# CheeseCake-BMI270-RV.net
KiCad netlist of a schematic drawn in EasyEDA Pro
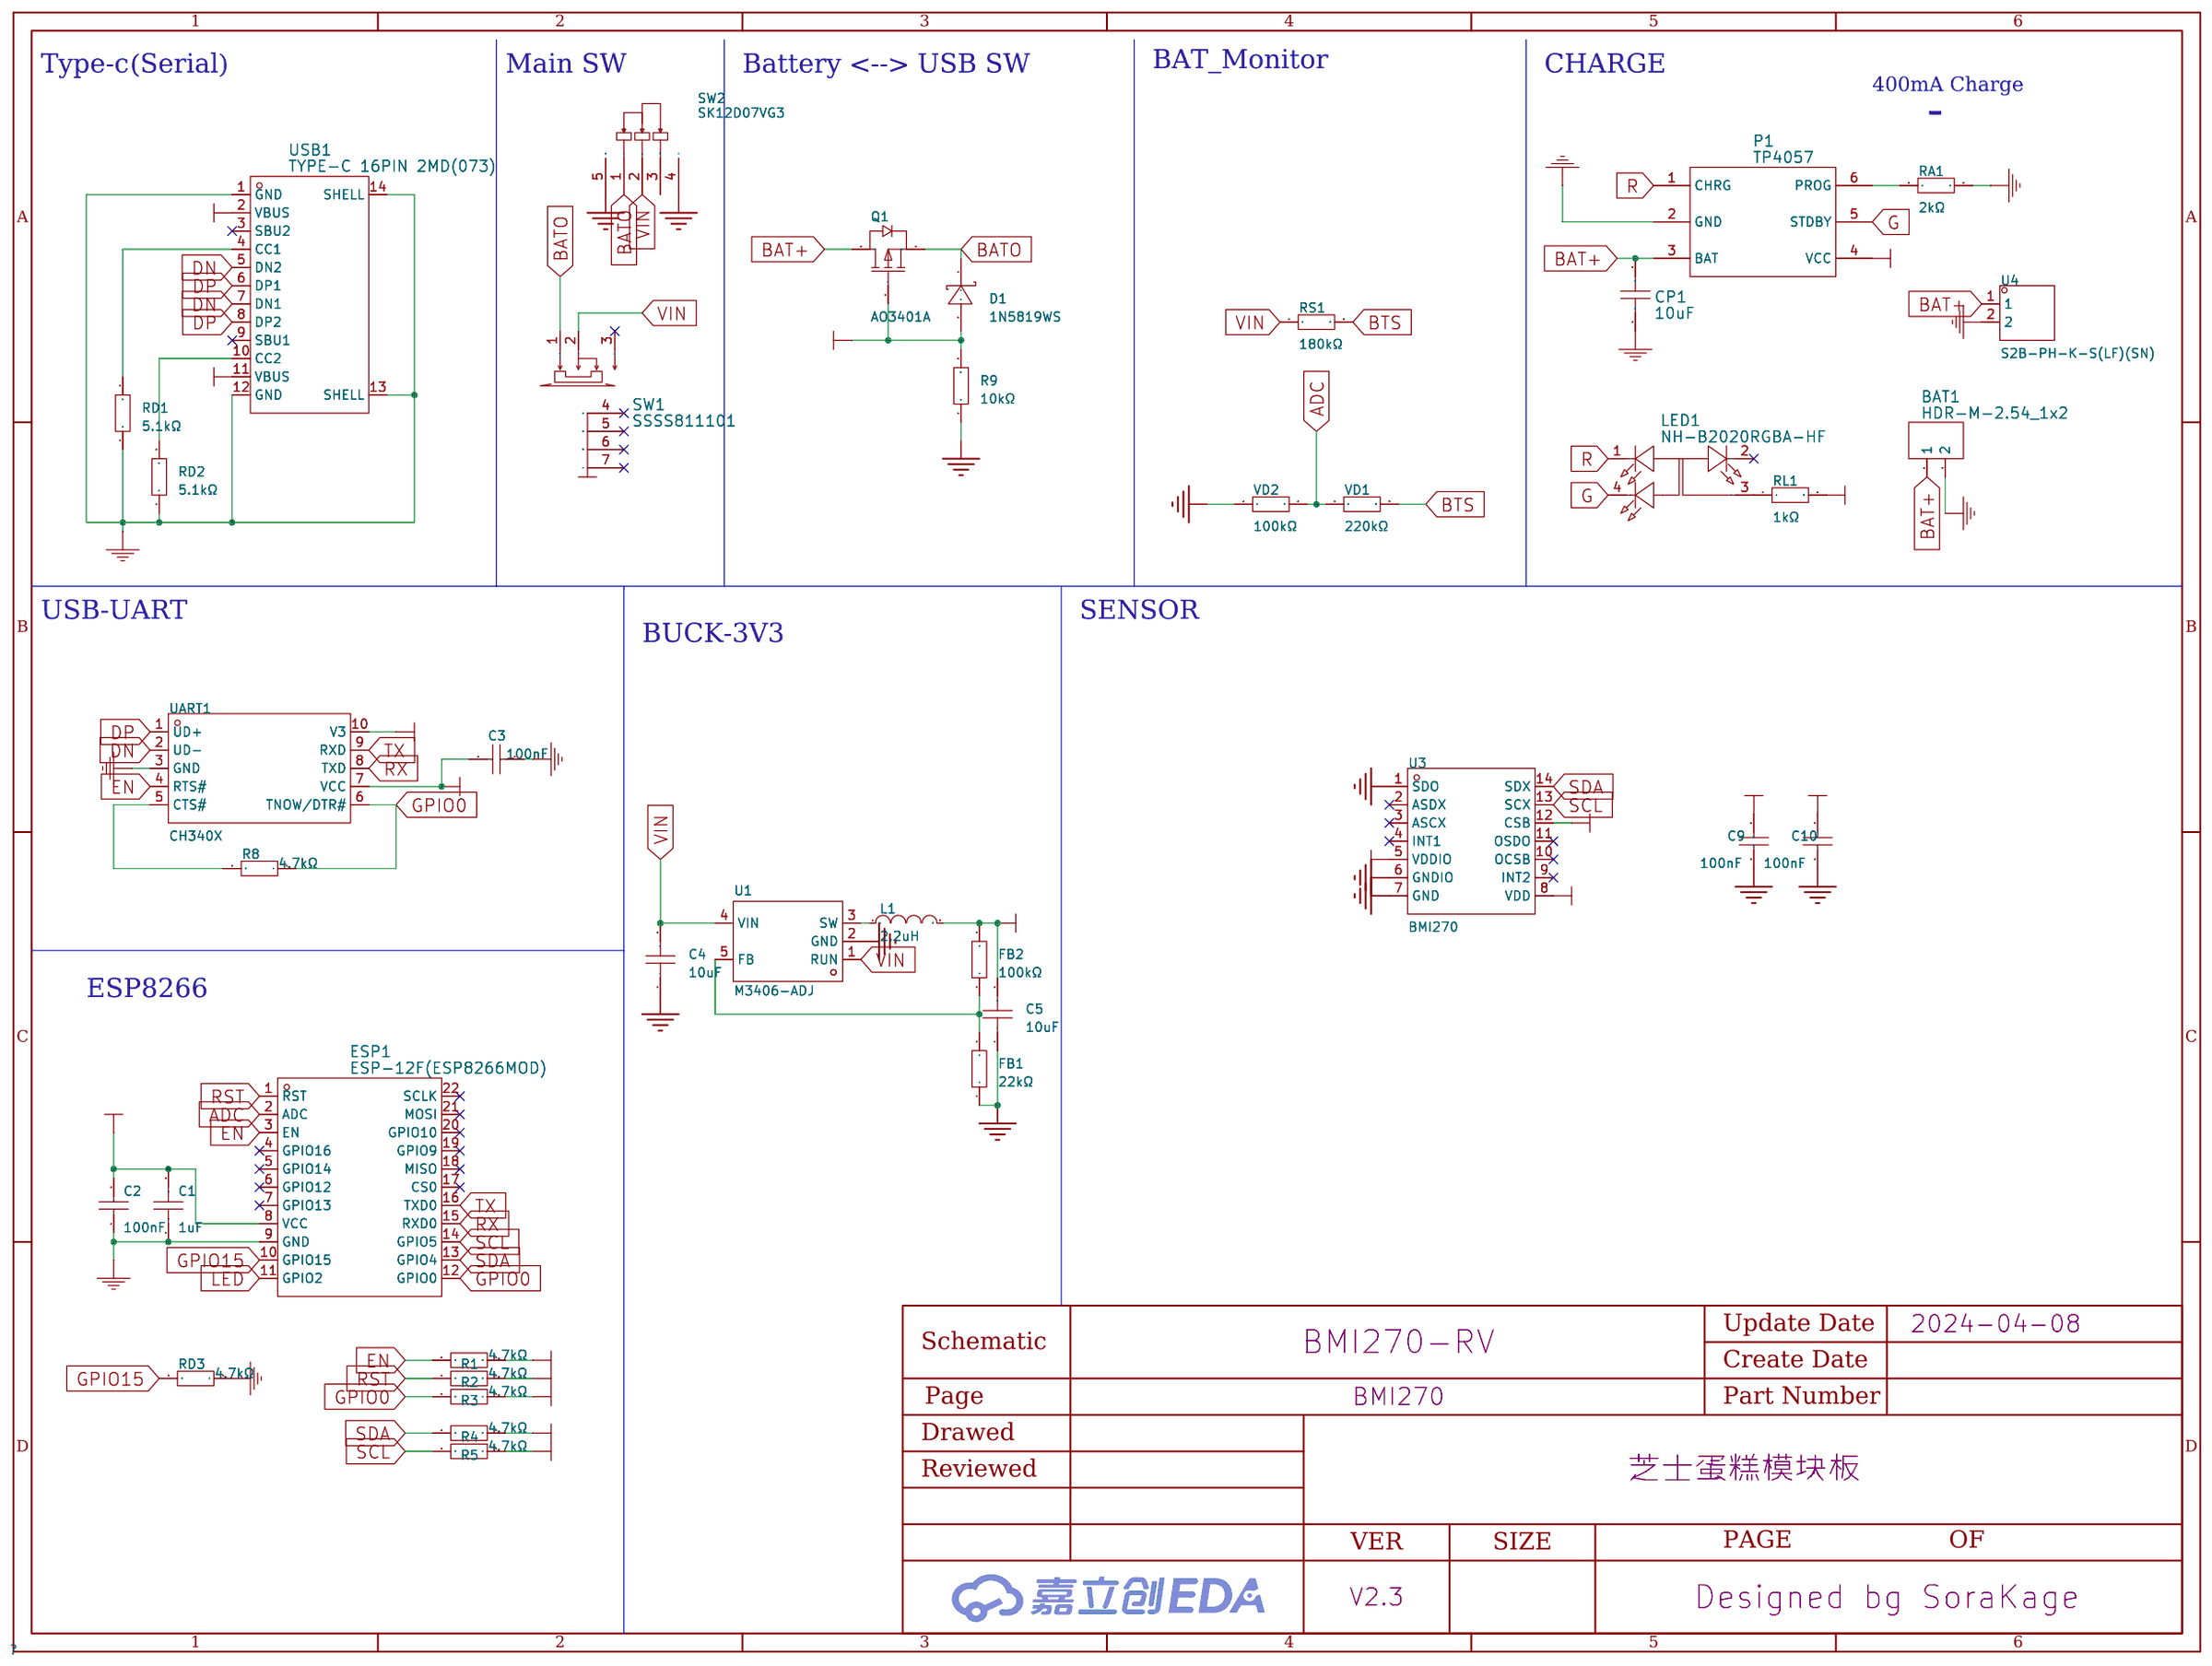
[diagram p0: schematic sheet]

(export (version "E")
  (design (tool "Eeschema 10.0.6"))
  (components
    (comp (ref "BAT1")
      (value "HDR-M-2.54_1x2")
      (footprint "easyedapro:HDR-M-2.54_1X2")
      (libsource (lib "easyedapro") (part "HDR-M-2.54_1x2"))
    )
    (comp (ref "C1")
      (value "1uF")
      (footprint "easyedapro:C0402")
      (description "容值:1uF;精度:±10%;额定电压:25V;材质(温度系数):X5R;")
      (fields
        (field (name "Manufacturer Part") "CL05A105KA5NQNC")
        (field (name "Manufacturer") "SAMSUNG(三星)")
      )
      (libsource (lib "easyedapro") (part "CL05A105KA5NQNC"))
    )
    (comp (ref "C2")
      (value "100nF")
      (footprint "easyedapro:C0402")
      (description "容值:100nF;精度:±10%;额定电压:16V;材质(温度系数):X7R;")
      (fields
        (field (name "Manufacturer Part") "CL05B104KO5NNNC")
        (field (name "Manufacturer") "SAMSUNG(三星)")
      )
      (libsource (lib "easyedapro") (part "CL05B104KO5NNNC"))
    )
    (comp (ref "C3")
      (value "100nF")
      (footprint "easyedapro:C0402")
      (description "容值:100nF;精度:±10%;额定电压:16V;材质(温度系数):X7R;")
      (fields
        (field (name "Manufacturer Part") "CL05B104KO5NNNC")
        (field (name "Manufacturer") "SAMSUNG(三星)")
      )
      (libsource (lib "easyedapro") (part "CL05B104KO5NNNC"))
    )
    (comp (ref "C4")
      (value "10uF")
      (footprint "easyedapro:C0603")
      (description "容值:10uF;精度:±10%;额定电压:10V;材质(温度系数):X5R;")
      (fields
        (field (name "Manufacturer Part") "CL10A106KP8NNNC")
        (field (name "Manufacturer") "SAMSUNG(三星)")
      )
      (libsource (lib "easyedapro") (part "CL10A106KP8NNNC"))
    )
    (comp (ref "C5")
      (value "10uF")
      (footprint "easyedapro:C0603")
      (description "容值:10uF;精度:±10%;额定电压:10V;材质(温度系数):X5R;")
      (fields
        (field (name "Manufacturer Part") "CL10A106KP8NNNC")
        (field (name "Manufacturer") "SAMSUNG(三星)")
      )
      (libsource (lib "easyedapro") (part "CL10A106KP8NNNC"))
    )
    (comp (ref "C9")
      (value "100nF")
      (footprint "easyedapro:C0402")
      (description "容值:100nF;精度:±10%;额定电压:16V;材质(温度系数):X7R;")
      (fields
        (field (name "Manufacturer Part") "CL05B104KO5NNNC")
        (field (name "Manufacturer") "SAMSUNG(三星)")
      )
      (libsource (lib "easyedapro") (part "CL05B104KO5NNNC"))
    )
    (comp (ref "C10")
      (value "100nF")
      (footprint "easyedapro:C0402")
      (description "容值:100nF;精度:±10%;额定电压:16V;材质(温度系数):X7R;")
      (fields
        (field (name "Manufacturer Part") "CL05B104KO5NNNC")
        (field (name "Manufacturer") "SAMSUNG(三星)")
      )
      (libsource (lib "easyedapro") (part "CL05B104KO5NNNC"))
    )
    (comp (ref "CP1")
      (value "10uF")
      (footprint "easyedapro:C0603")
      (fields
        (field (name "Manufacturer Part") "CL10A106KP8NNNC")
        (field (name "Manufacturer") "SAMSUNG(三星)")
      )
      (libsource (lib "easyedapro") (part "10uF"))
    )
    (comp (ref "D1")
      (value "1N5819WS")
      (footprint "easyedapro:SOD-323_L1.8-W1.3-LS2.5-RD")
      (description "直流反向耐压(Vr):40V;平均整流电流(Io):1A;正向压降(Vf):600mV@1A;")
      (fields (field (name "Manufacturer") "Hottech(合科泰)"))
      (libsource (lib "easyedapro") (part "1N5819WS"))
    )
    (comp (ref "ESP1")
      (value "ESP-12F(ESP8266MOD)")
      (fields (field (name "Manufacturer") "Ai-Thinker"))
      (libsource (lib "easyedapro") (part "ESP-12F(ESP8266MOD)"))
    )
    (comp (ref "FB1")
      (value "22kΩ")
      (footprint "easyedapro:R0402")
      (description "电阻类型:厚膜电阻;阻值:22kΩ;精度:±1%;功率:62.5mW;")
      (fields
        (field (name "Manufacturer Part") "0402WGF2202TCE")
        (field (name "Manufacturer") "UNI-ROYAL(厚声)")
      )
      (libsource (lib "easyedapro") (part "0402WGF2202TCE"))
    )
    (comp (ref "FB2")
      (value "100kΩ")
      (footprint "easyedapro:R0402")
      (description "电阻类型:厚膜电阻;阻值:100kΩ;精度:±1%;功率:62.5mW;")
      (fields
        (field (name "Manufacturer Part") "0402WGF1003TCE")
        (field (name "Manufacturer") "UNI-ROYAL(厚声)")
      )
      (libsource (lib "easyedapro") (part "0402WGF1003TCE"))
    )
    (comp (ref "L1")
      (value "2.2uH")
      (footprint "easyedapro:IND-SMD_L2.5-W2.0_YXMBL252010P")
      (description "类型:一体成型电感;电感值:2.2uH;精度:±20%;额定电流:2.1A;饱和电流(Isat):3A;")
      (fields (field (name "Manufacturer Part") "APH252010T2R2M") (field (name "Manufacturer") "APV(爱普微)"))
      (libsource (lib "easyedapro") (part "APH252010T2R2M"))
    )
    (comp (ref "LED1")
      (value "NH-B2020RGBA-HF")
      (footprint "easyedapro:LED-ARRAY-SMD_4P-L2.1-W2.1-TL_NH-B2020RGBA")
      (fields (field (name "Manufacturer") "国星光电"))
      (libsource (lib "easyedapro") (part "NH-B2020RGBA-HF"))
    )
    (comp (ref "P1")
      (value "TP4057")
      (fields
        (field (name "Manufacturer Part") "TP4057-42-SOT26-R")
        (field (name "Manufacturer") "TOPPOWER(南京拓微)")
      )
      (libsource (lib "easyedapro") (part "TP4057"))
    )
    (comp (ref "Q1")
      (value "AO3401A")
      (footprint "easyedapro:SOT-23_L2.9-W1.3-P1.90-LS2.4-BR")
      (description "类型:P沟道;漏源电压(Vdss):30V;连续漏极电流(Id):4A;功率(Pd):1.4W;导通电阻(RDS(on)@Vgs,Id):44mΩ@10V,4.3A;")
      (fields (field (name "Manufacturer") "AOS"))
      (libsource (lib "easyedapro") (part "AO3401A"))
    )
    (comp (ref "R1")
      (value "4.7kΩ")
      (footprint "easyedapro:R0402")
      (description "电阻类型:厚膜电阻;阻值:4.7kΩ;精度:±1%;功率:62.5mW;")
      (fields
        (field (name "Manufacturer Part") "0402WGF4701TCE")
        (field (name "Manufacturer") "UNI-ROYAL(厚声)")
      )
      (libsource (lib "easyedapro") (part "0402WGF4701TCE"))
    )
    (comp (ref "R2")
      (value "4.7kΩ")
      (footprint "easyedapro:R0402")
      (description "电阻类型:厚膜电阻;阻值:4.7kΩ;精度:±1%;功率:62.5mW;")
      (fields
        (field (name "Manufacturer Part") "0402WGF4701TCE")
        (field (name "Manufacturer") "UNI-ROYAL(厚声)")
      )
      (libsource (lib "easyedapro") (part "0402WGF4701TCE"))
    )
    (comp (ref "R3")
      (value "4.7kΩ")
      (footprint "easyedapro:R0402")
      (description "电阻类型:厚膜电阻;阻值:4.7kΩ;精度:±1%;功率:62.5mW;")
      (fields
        (field (name "Manufacturer Part") "0402WGF4701TCE")
        (field (name "Manufacturer") "UNI-ROYAL(厚声)")
      )
      (libsource (lib "easyedapro") (part "0402WGF4701TCE"))
    )
    (comp (ref "R4")
      (value "4.7kΩ")
      (footprint "easyedapro:R0402")
      (description "电阻类型:厚膜电阻;阻值:4.7kΩ;精度:±1%;功率:62.5mW;")
      (fields
        (field (name "Manufacturer Part") "0402WGF4701TCE")
        (field (name "Manufacturer") "UNI-ROYAL(厚声)")
      )
      (libsource (lib "easyedapro") (part "0402WGF4701TCE"))
    )
    (comp (ref "R5")
      (value "4.7kΩ")
      (footprint "easyedapro:R0402")
      (description "电阻类型:厚膜电阻;阻值:4.7kΩ;精度:±1%;功率:62.5mW;")
      (fields
        (field (name "Manufacturer Part") "0402WGF4701TCE")
        (field (name "Manufacturer") "UNI-ROYAL(厚声)")
      )
      (libsource (lib "easyedapro") (part "0402WGF4701TCE"))
    )
    (comp (ref "R8")
      (value "4.7kΩ")
      (footprint "easyedapro:R0402")
      (description "电阻类型:厚膜电阻;阻值:4.7kΩ;精度:±1%;功率:62.5mW;")
      (fields
        (field (name "Manufacturer Part") "0402WGF4701TCE")
        (field (name "Manufacturer") "UNI-ROYAL(厚声)")
      )
      (libsource (lib "easyedapro") (part "0402WGF4701TCE"))
    )
    (comp (ref "R9")
      (value "10kΩ")
      (footprint "easyedapro:R0402")
      (description "电阻类型:厚膜电阻;阻值:10kΩ;精度:±1%;功率:62.5mW;")
      (fields
        (field (name "Manufacturer Part") "0402WGF1002TCE")
        (field (name "Manufacturer") "UNI-ROYAL(厚声)")
      )
      (libsource (lib "easyedapro") (part "0402WGF1002TCE"))
    )
    (comp (ref "RA1")
      (value "2kΩ")
      (footprint "easyedapro:R0402")
      (description "电阻类型:厚膜电阻;阻值:2kΩ;精度:±1%;功率:62.5mW;")
      (fields
        (field (name "Manufacturer Part") "0402WGF2001TCE")
        (field (name "Manufacturer") "UNI-ROYAL(厚声)")
      )
      (libsource (lib "easyedapro") (part "0402WGF2001TCE"))
    )
    (comp (ref "RD1")
      (value "5.1kΩ")
      (footprint "easyedapro:R0402")
      (description "电阻类型:厚膜电阻;阻值:5.1kΩ;精度:±1%;功率:62.5mW;")
      (fields
        (field (name "Manufacturer Part") "0402WGF5101TCE")
        (field (name "Manufacturer") "UNI-ROYAL(厚声)")
      )
      (libsource (lib "easyedapro") (part "0402WGF5101TCE"))
    )
    (comp (ref "RD2")
      (value "5.1kΩ")
      (footprint "easyedapro:R0402")
      (description "电阻类型:厚膜电阻;阻值:5.1kΩ;精度:±1%;功率:62.5mW;")
      (fields
        (field (name "Manufacturer Part") "0402WGF5101TCE")
        (field (name "Manufacturer") "UNI-ROYAL(厚声)")
      )
      (libsource (lib "easyedapro") (part "0402WGF5101TCE"))
    )
    (comp (ref "RD3")
      (value "4.7kΩ")
      (footprint "easyedapro:R0402")
      (description "电阻类型:厚膜电阻;阻值:4.7kΩ;精度:±1%;功率:62.5mW;")
      (fields
        (field (name "Manufacturer Part") "0402WGF4701TCE")
        (field (name "Manufacturer") "UNI-ROYAL(厚声)")
      )
      (libsource (lib "easyedapro") (part "0402WGF4701TCE"))
    )
    (comp (ref "RL1")
      (value "1kΩ")
      (footprint "easyedapro:R0402")
      (description "电阻类型:厚膜电阻;阻值:1kΩ;精度:±1%;功率:62.5mW;")
      (fields
        (field (name "Manufacturer Part") "0402WGF1001TCE")
        (field (name "Manufacturer") "UNI-ROYAL(厚声)")
      )
      (libsource (lib "easyedapro") (part "0402WGF1001TCE"))
    )
    (comp (ref "RS1")
      (value "180kΩ")
      (footprint "easyedapro:R0402")
      (description "阻值:180kΩ;精度:±1%;功率:62.5mW;温度系数:±100ppm/°C;电阻类型:厚膜电阻;")
      (fields
        (field (name "Manufacturer Part") "0402WGF1803TCE")
        (field (name "Manufacturer") "UNI-ROYAL(厚声)")
      )
      (libsource (lib "easyedapro") (part "0402WGF1803TCE"))
    )
    (comp (ref "SW1")
      (value "SSSS811101")
      (footprint "easyedapro:SW-SMD_SSSS811101")
      (fields (field (name "Manufacturer") "ALPSALPINE(阿尔卑斯阿尔派)"))
      (libsource (lib "easyedapro") (part "SSSS811101"))
    )
    (comp (ref "SW2")
      (value "SK12D07VG3")
      (footprint "easyedapro:SW-TH_SK12D07VG3")
      (description "电路结构:单刀双掷;安装方式:侧插;开关颜色:-;额定电流(DC):500mA;额定电压(DC):50V;额定电流(AC):-;额定电压(AC):-;机械寿命:5千次;")
      (fields (field (name "Manufacturer") "SHOU HAN(首韩)"))
      (libsource (lib "easyedapro") (part "SK12D07VG3_C431547"))
    )
    (comp (ref "U1")
      (value "M3406-ADJ")
      (footprint "easyedapro:SOT-23-5_L3.0-W1.7-P0.95-LS2.8-BR")
      (description "功能类型:降压型;同步整流:-;输出通道数:-;拓扑结构:-;输入电压:-;输出电流(最大值):-;开关频率:-;")
      (fields (field (name "Manufacturer") "西安航天民芯"))
      (libsource (lib "easyedapro") (part "M3406"))
    )
    (comp (ref "U3")
      (value "BMI270")
      (footprint "easyedapro:LGA-14_L3.0-W2.5-P0.50-BR")
      (description "IMU-惯性测量单元")
      (fields (field (name "Manufacturer") "Bosch(博世)"))
      (libsource (lib "easyedapro") (part "BMI270"))
    )
    (comp (ref "U4")
      (value "S2B-PH-K-S(LF)(SN)")
      (footprint "easyedapro:CONN-TH_S2B-PH-K-S-LF-SN")
      (description "插针结构:1x2P;间距:2mm;安装方式:弯插;参考系列:PH;总PIN数:2P;排数:1;每排PIN数:2;行距:-;触头材质:黄铜;")
      (fields (field (name "Manufacturer") "JST"))
      (libsource (lib "easyedapro") (part "S2B-PH-K-S(LF)(SN)"))
    )
    (comp (ref "UART1")
      (value "CH340X")
      (footprint "easyedapro:MSOP-10_L3.0-W3.0-P0.50-LS5.0-BL")
      (fields (field (name "Manufacturer") "WCH(南京沁恒)"))
      (libsource (lib "easyedapro") (part "CH340X"))
    )
    (comp (ref "USB1")
      (value "TYPE-C 16PIN 2MD(073)")
      (footprint "easyedapro:USB-C-SMD_TYPE-C-6PIN-2MD-073")
      (fields (field (name "Manufacturer") "SHOU HAN(首韩)"))
      (libsource (lib "easyedapro") (part "TYPE-C 16PIN 2MD(073)"))
    )
    (comp (ref "VD1")
      (value "220kΩ")
      (footprint "easyedapro:R0402")
      (description "电阻类型:厚膜电阻;阻值:220kΩ;精度:±1%;功率:62.5mW;")
      (fields
        (field (name "Manufacturer Part") "0402WGF2203TCE")
        (field (name "Manufacturer") "UNI-ROYAL(厚声)")
      )
      (libsource (lib "easyedapro") (part "0402WGF2203TCE"))
    )
    (comp (ref "VD2")
      (value "100kΩ")
      (footprint "easyedapro:R0402")
      (description "电阻类型:厚膜电阻;阻值:100kΩ;精度:±1%;功率:62.5mW;")
      (fields
        (field (name "Manufacturer Part") "0402WGF1003TCE")
        (field (name "Manufacturer") "UNI-ROYAL(厚声)")
      )
      (libsource (lib "easyedapro") (part "0402WGF1003TCE"))
    )
  )
  (nets
    (net (code "1") (name "+5V") (class "Default")
      (node (ref "D1") (pin "2") (pinfunction "A_2") (pintype "unspecified"))
      (node (ref "P1") (pin "4") (pinfunction "VCC_4") (pintype "input"))
      (node (ref "Q1") (pin "1") (pinfunction "G_1") (pintype "input"))
      (node (ref "R9") (pin "2") (pinfunction "2_2") (pintype "input"))
      (node (ref "RL1") (pin "2") (pinfunction "2_2") (pintype "input"))
      (node (ref "USB1") (pin "11") (pinfunction "VBUS_11") (pintype "input"))
      (node (ref "USB1") (pin "2") (pinfunction "VBUS_2") (pintype "input"))
    )
    (net (code "2") (name "3V3") (class "Default")
      (node (ref "C1") (pin "2") (pinfunction "2_2") (pintype "unspecified"))
      (node (ref "C10") (pin "1") (pinfunction "1_1") (pintype "input"))
      (node (ref "C2") (pin "2") (pinfunction "2_2") (pintype "input"))
      (node (ref "C3") (pin "2") (pinfunction "2_2") (pintype "input"))
      (node (ref "C5") (pin "2") (pinfunction "2_2") (pintype "unspecified"))
      (node (ref "C9") (pin "1") (pinfunction "1_1") (pintype "input"))
      (node (ref "ESP1") (pin "8") (pinfunction "VCC_8") (pintype "input"))
      (node (ref "FB2") (pin "2") (pinfunction "2_2") (pintype "input"))
      (node (ref "L1") (pin "2") (pinfunction "2_2") (pintype "unspecified"))
      (node (ref "R1") (pin "1") (pinfunction "1_1") (pintype "input"))
      (node (ref "R2") (pin "1") (pinfunction "1_1") (pintype "input"))
      (node (ref "R3") (pin "1") (pinfunction "1_1") (pintype "input"))
      (node (ref "R4") (pin "1") (pinfunction "1_1") (pintype "input"))
      (node (ref "R5") (pin "1") (pinfunction "1_1") (pintype "input"))
      (node (ref "U3") (pin "12") (pinfunction "CSB_12") (pintype "input"))
      (node (ref "U3") (pin "5") (pinfunction "VDDIO_5") (pintype "input"))
      (node (ref "U3") (pin "8") (pinfunction "VDD_8") (pintype "input"))
      (node (ref "UART1") (pin "10") (pinfunction "V3_10") (pintype "unspecified"))
      (node (ref "UART1") (pin "7") (pinfunction "VCC_7") (pintype "unspecified"))
    )
    (net (code "3") (name "ADC") (class "Default")
      (node (ref "ESP1") (pin "2") (pinfunction "ADC_2") (pintype "input"))
      (node (ref "VD1") (pin "1") (pinfunction "1_1") (pintype "input"))
      (node (ref "VD2") (pin "2") (pinfunction "2_2") (pintype "input"))
    )
    (net (code "4") (name "BAT+") (class "Default")
      (node (ref "BAT1") (pin "1") (pinfunction "1_1") (pintype "input"))
      (node (ref "CP1") (pin "2") (pinfunction "2_2") (pintype "input"))
      (node (ref "P1") (pin "3") (pinfunction "BAT_3") (pintype "input"))
      (node (ref "Q1") (pin "3") (pinfunction "D_3") (pintype "input"))
      (node (ref "U4") (pin "1") (pinfunction "1_1") (pintype "unspecified"))
    )
    (net (code "5") (name "BATO") (class "Default")
      (node (ref "D1") (pin "1") (pinfunction "K_1") (pintype "unspecified"))
      (node (ref "Q1") (pin "2") (pinfunction "S_2") (pintype "input"))
      (node (ref "SW1") (pin "1") (pinfunction "1_1") (pintype "input"))
      (node (ref "SW2") (pin "1") (pinfunction "1_1") (pintype "unspecified"))
    )
    (net (code "6") (name "BTS") (class "Default")
      (node (ref "RS1") (pin "2") (pinfunction "2_2") (pintype "input"))
      (node (ref "VD1") (pin "2") (pinfunction "2_2") (pintype "input"))
    )
    (net (code "7") (name "DN") (class "Default")
      (node (ref "UART1") (pin "2") (pinfunction "UD-_2") (pintype "unspecified"))
      (node (ref "USB1") (pin "5") (pinfunction "DN2_5") (pintype "input"))
      (node (ref "USB1") (pin "7") (pinfunction "DN1_7") (pintype "input"))
    )
    (net (code "8") (name "DP") (class "Default")
      (node (ref "UART1") (pin "1") (pinfunction "UD+_1") (pintype "unspecified"))
      (node (ref "USB1") (pin "6") (pinfunction "DP1_6") (pintype "input"))
      (node (ref "USB1") (pin "8") (pinfunction "DP2_8") (pintype "input"))
    )
    (net (code "9") (name "EN") (class "Default")
      (node (ref "ESP1") (pin "3") (pinfunction "EN_3") (pintype "input"))
      (node (ref "R1") (pin "2") (pinfunction "2_2") (pintype "input"))
      (node (ref "UART1") (pin "4") (pinfunction "RTS#_4") (pintype "unspecified"))
    )
    (net (code "10") (name "G") (class "Default")
      (node (ref "LED1") (pin "4") (pinfunction "-_4") (pintype "input"))
      (node (ref "P1") (pin "5") (pinfunction "STDBY_5") (pintype "input"))
    )
    (net (code "11") (name "GND") (class "Default")
      (node (ref "BAT1") (pin "2") (pinfunction "2_2") (pintype "input"))
      (node (ref "C1") (pin "1") (pinfunction "1_1") (pintype "unspecified"))
      (node (ref "C10") (pin "2") (pinfunction "2_2") (pintype "input"))
      (node (ref "C2") (pin "1") (pinfunction "1_1") (pintype "input"))
      (node (ref "C3") (pin "1") (pinfunction "1_1") (pintype "input"))
      (node (ref "C4") (pin "1") (pinfunction "1_1") (pintype "unspecified"))
      (node (ref "C5") (pin "1") (pinfunction "1_1") (pintype "unspecified"))
      (node (ref "C9") (pin "2") (pinfunction "2_2") (pintype "input"))
      (node (ref "CP1") (pin "1") (pinfunction "1_1") (pintype "input"))
      (node (ref "ESP1") (pin "9") (pinfunction "GND_9") (pintype "input"))
      (node (ref "FB1") (pin "1") (pinfunction "1_1") (pintype "input"))
      (node (ref "P1") (pin "2") (pinfunction "GND_2") (pintype "input"))
      (node (ref "R9") (pin "1") (pinfunction "1_1") (pintype "input"))
      (node (ref "RA1") (pin "2") (pinfunction "2_2") (pintype "input"))
      (node (ref "RD1") (pin "1") (pinfunction "1_1") (pintype "input"))
      (node (ref "RD2") (pin "1") (pinfunction "1_1") (pintype "input"))
      (node (ref "RD3") (pin "1") (pinfunction "1_1") (pintype "input"))
      (node (ref "SW2") (pin "4") (pinfunction "4_4") (pintype "unspecified"))
      (node (ref "SW2") (pin "5") (pinfunction "5_5") (pintype "unspecified"))
      (node (ref "U1") (pin "2") (pinfunction "GND_2") (pintype "input"))
      (node (ref "U3") (pin "1") (pinfunction "SDO_1") (pintype "input"))
      (node (ref "U3") (pin "6") (pinfunction "GNDIO_6") (pintype "input"))
      (node (ref "U3") (pin "7") (pinfunction "GND_7") (pintype "input"))
      (node (ref "U4") (pin "2") (pinfunction "2_2") (pintype "unspecified"))
      (node (ref "UART1") (pin "3") (pinfunction "GND_3") (pintype "unspecified"))
      (node (ref "USB1") (pin "1") (pinfunction "GND_1") (pintype "input"))
      (node (ref "USB1") (pin "12") (pinfunction "GND_12") (pintype "input"))
      (node (ref "USB1") (pin "13") (pinfunction "SHELL_13") (pintype "input"))
      (node (ref "USB1") (pin "14") (pinfunction "SHELL_14") (pintype "input"))
      (node (ref "VD2") (pin "1") (pinfunction "1_1") (pintype "input"))
    )
    (net (code "12") (name "GPIO0") (class "Default")
      (node (ref "ESP1") (pin "12") (pinfunction "GPIO0_12") (pintype "input"))
      (node (ref "R3") (pin "2") (pinfunction "2_2") (pintype "input"))
      (node (ref "R8") (pin "1") (pinfunction "1_1") (pintype "input"))
      (node (ref "UART1") (pin "6") (pinfunction "TNOW/DTR#_6") (pintype "unspecified"))
    )
    (net (code "13") (name "GPIO15") (class "Default")
      (node (ref "ESP1") (pin "10") (pinfunction "GPIO15_10") (pintype "input"))
      (node (ref "RD3") (pin "2") (pinfunction "2_2") (pintype "input"))
    )
    (net (code "14") (name "LED") (class "Default")
      (node (ref "ESP1") (pin "11") (pinfunction "GPIO2_11") (pintype "input"))
    )
    (net (code "15") (name "Net-(LED1-+)") (class "Default")
      (node (ref "LED1") (pin "3") (pinfunction "+_3") (pintype "input"))
      (node (ref "RL1") (pin "1") (pinfunction "1_1") (pintype "input"))
    )
    (net (code "16") (name "Net-(P1-PROG)") (class "Default")
      (node (ref "P1") (pin "6") (pinfunction "PROG_6") (pintype "input"))
      (node (ref "RA1") (pin "1") (pinfunction "1_1") (pintype "input"))
    )
    (net (code "17") (name "Net-(U1-FB)") (class "Default")
      (node (ref "FB1") (pin "2") (pinfunction "2_2") (pintype "input"))
      (node (ref "FB2") (pin "1") (pinfunction "1_1") (pintype "input"))
      (node (ref "U1") (pin "5") (pinfunction "FB_5") (pintype "input"))
    )
    (net (code "18") (name "Net-(U1-SW)") (class "Default")
      (node (ref "L1") (pin "1") (pinfunction "1_1") (pintype "unspecified"))
      (node (ref "U1") (pin "3") (pinfunction "SW_3") (pintype "input"))
    )
    (net (code "19") (name "Net-(UART1-CTS#)") (class "Default")
      (node (ref "R8") (pin "2") (pinfunction "2_2") (pintype "input"))
      (node (ref "UART1") (pin "5") (pinfunction "CTS#_5") (pintype "unspecified"))
    )
    (net (code "20") (name "Net-(USB1-CC1)") (class "Default")
      (node (ref "RD1") (pin "2") (pinfunction "2_2") (pintype "input"))
      (node (ref "USB1") (pin "4") (pinfunction "CC1_4") (pintype "input"))
    )
    (net (code "21") (name "Net-(USB1-CC2)") (class "Default")
      (node (ref "RD2") (pin "2") (pinfunction "2_2") (pintype "input"))
      (node (ref "USB1") (pin "10") (pinfunction "CC2_10") (pintype "input"))
    )
    (net (code "22") (name "R") (class "Default")
      (node (ref "LED1") (pin "1") (pinfunction "-_1") (pintype "input"))
      (node (ref "P1") (pin "1") (pinfunction "CHRG_1") (pintype "input"))
    )
    (net (code "23") (name "RST") (class "Default")
      (node (ref "ESP1") (pin "1") (pinfunction "RST_1") (pintype "input"))
      (node (ref "R2") (pin "2") (pinfunction "2_2") (pintype "input"))
    )
    (net (code "24") (name "RX") (class "Default")
      (node (ref "ESP1") (pin "15") (pinfunction "RXD0_15") (pintype "input"))
      (node (ref "UART1") (pin "8") (pinfunction "TXD_8") (pintype "unspecified"))
    )
    (net (code "25") (name "SCL") (class "Default")
      (node (ref "ESP1") (pin "14") (pinfunction "GPIO5_14") (pintype "input"))
      (node (ref "R5") (pin "2") (pinfunction "2_2") (pintype "input"))
      (node (ref "U3") (pin "13") (pinfunction "SCX_13") (pintype "input"))
    )
    (net (code "26") (name "SDA") (class "Default")
      (node (ref "ESP1") (pin "13") (pinfunction "GPIO4_13") (pintype "input"))
      (node (ref "R4") (pin "2") (pinfunction "2_2") (pintype "input"))
      (node (ref "U3") (pin "14") (pinfunction "SDX_14") (pintype "input"))
    )
    (net (code "27") (name "TX") (class "Default")
      (node (ref "ESP1") (pin "16") (pinfunction "TXD0_16") (pintype "input"))
      (node (ref "UART1") (pin "9") (pinfunction "RXD_9") (pintype "unspecified"))
    )
    (net (code "28") (name "VIN") (class "Default")
      (node (ref "C4") (pin "2") (pinfunction "2_2") (pintype "unspecified"))
      (node (ref "RS1") (pin "1") (pinfunction "1_1") (pintype "input"))
      (node (ref "SW1") (pin "2") (pinfunction "2_2") (pintype "input"))
      (node (ref "SW2") (pin "2") (pinfunction "2_2") (pintype "unspecified"))
      (node (ref "U1") (pin "1") (pinfunction "RUN_1") (pintype "input"))
      (node (ref "U1") (pin "4") (pinfunction "VIN_4") (pintype "input"))
    )
    (net (code "29") (name "unconnected-(ESP1-CS0-Pad17)") (class "Default")
      (node (ref "ESP1") (pin "17") (pinfunction "CS0_17") (pintype "input+no_connect"))
    )
    (net (code "30") (name "unconnected-(ESP1-GPIO9-Pad19)") (class "Default")
      (node (ref "ESP1") (pin "19") (pinfunction "GPIO9_19") (pintype "input+no_connect"))
    )
    (net (code "31") (name "unconnected-(ESP1-GPIO10-Pad20)") (class "Default")
      (node (ref "ESP1") (pin "20") (pinfunction "GPIO10_20") (pintype "input+no_connect"))
    )
    (net (code "32") (name "unconnected-(ESP1-GPIO12-Pad6)") (class "Default")
      (node (ref "ESP1") (pin "6") (pinfunction "GPIO12_6") (pintype "input+no_connect"))
    )
    (net (code "33") (name "unconnected-(ESP1-GPIO13-Pad7)") (class "Default")
      (node (ref "ESP1") (pin "7") (pinfunction "GPIO13_7") (pintype "input+no_connect"))
    )
    (net (code "34") (name "unconnected-(ESP1-GPIO14-Pad5)") (class "Default")
      (node (ref "ESP1") (pin "5") (pinfunction "GPIO14_5") (pintype "input+no_connect"))
    )
    (net (code "35") (name "unconnected-(ESP1-GPIO16-Pad4)") (class "Default")
      (node (ref "ESP1") (pin "4") (pinfunction "GPIO16_4") (pintype "input+no_connect"))
    )
    (net (code "36") (name "unconnected-(ESP1-MISO-Pad18)") (class "Default")
      (node (ref "ESP1") (pin "18") (pinfunction "MISO_18") (pintype "input+no_connect"))
    )
    (net (code "37") (name "unconnected-(ESP1-MOSI-Pad21)") (class "Default")
      (node (ref "ESP1") (pin "21") (pinfunction "MOSI_21") (pintype "input+no_connect"))
    )
    (net (code "38") (name "unconnected-(ESP1-SCLK-Pad22)") (class "Default")
      (node (ref "ESP1") (pin "22") (pinfunction "SCLK_22") (pintype "input+no_connect"))
    )
    (net (code "39") (name "unconnected-(LED1---Pad2)") (class "Default")
      (node (ref "LED1") (pin "2") (pinfunction "-_2") (pintype "input+no_connect"))
    )
    (net (code "40") (name "unconnected-(SW1-Pad3)") (class "Default")
      (node (ref "SW1") (pin "3") (pinfunction "3_3") (pintype "input+no_connect"))
    )
    (net (code "41") (name "unconnected-(SW1-Pad4)") (class "Default")
      (node (ref "SW1") (pin "4") (pinfunction "4_4") (pintype "input+no_connect"))
    )
    (net (code "42") (name "unconnected-(SW1-Pad5)") (class "Default")
      (node (ref "SW1") (pin "5") (pinfunction "5_5") (pintype "input+no_connect"))
    )
    (net (code "43") (name "unconnected-(SW1-Pad6)") (class "Default")
      (node (ref "SW1") (pin "6") (pinfunction "6_6") (pintype "input+no_connect"))
    )
    (net (code "44") (name "unconnected-(SW1-Pad7)") (class "Default")
      (node (ref "SW1") (pin "7") (pinfunction "7_7") (pintype "input+no_connect"))
    )
    (net (code "45") (name "unconnected-(SW2-Pad3)") (class "Default")
      (node (ref "SW2") (pin "3") (pinfunction "3_3") (pintype "unspecified"))
    )
    (net (code "46") (name "unconnected-(U3-ASCX-Pad3)") (class "Default")
      (node (ref "U3") (pin "3") (pinfunction "ASCX_3") (pintype "input+no_connect"))
    )
    (net (code "47") (name "unconnected-(U3-ASDX-Pad2)") (class "Default")
      (node (ref "U3") (pin "2") (pinfunction "ASDX_2") (pintype "input+no_connect"))
    )
    (net (code "48") (name "unconnected-(U3-INT1-Pad4)") (class "Default")
      (node (ref "U3") (pin "4") (pinfunction "INT1_4") (pintype "input+no_connect"))
    )
    (net (code "49") (name "unconnected-(U3-INT2-Pad9)") (class "Default")
      (node (ref "U3") (pin "9") (pinfunction "INT2_9") (pintype "input+no_connect"))
    )
    (net (code "50") (name "unconnected-(U3-OCSB-Pad10)") (class "Default")
      (node (ref "U3") (pin "10") (pinfunction "OCSB_10") (pintype "input+no_connect"))
    )
    (net (code "51") (name "unconnected-(U3-OSDO-Pad11)") (class "Default")
      (node (ref "U3") (pin "11") (pinfunction "OSDO_11") (pintype "input+no_connect"))
    )
    (net (code "52") (name "unconnected-(USB1-SBU1-Pad9)") (class "Default")
      (node (ref "USB1") (pin "9") (pinfunction "SBU1_9") (pintype "input+no_connect"))
    )
    (net (code "53") (name "unconnected-(USB1-SBU2-Pad3)") (class "Default")
      (node (ref "USB1") (pin "3") (pinfunction "SBU2_3") (pintype "input+no_connect"))
    )
  )
)
